# lna-plug.net
KiCad netlist of a schematic drawn in EAGLE
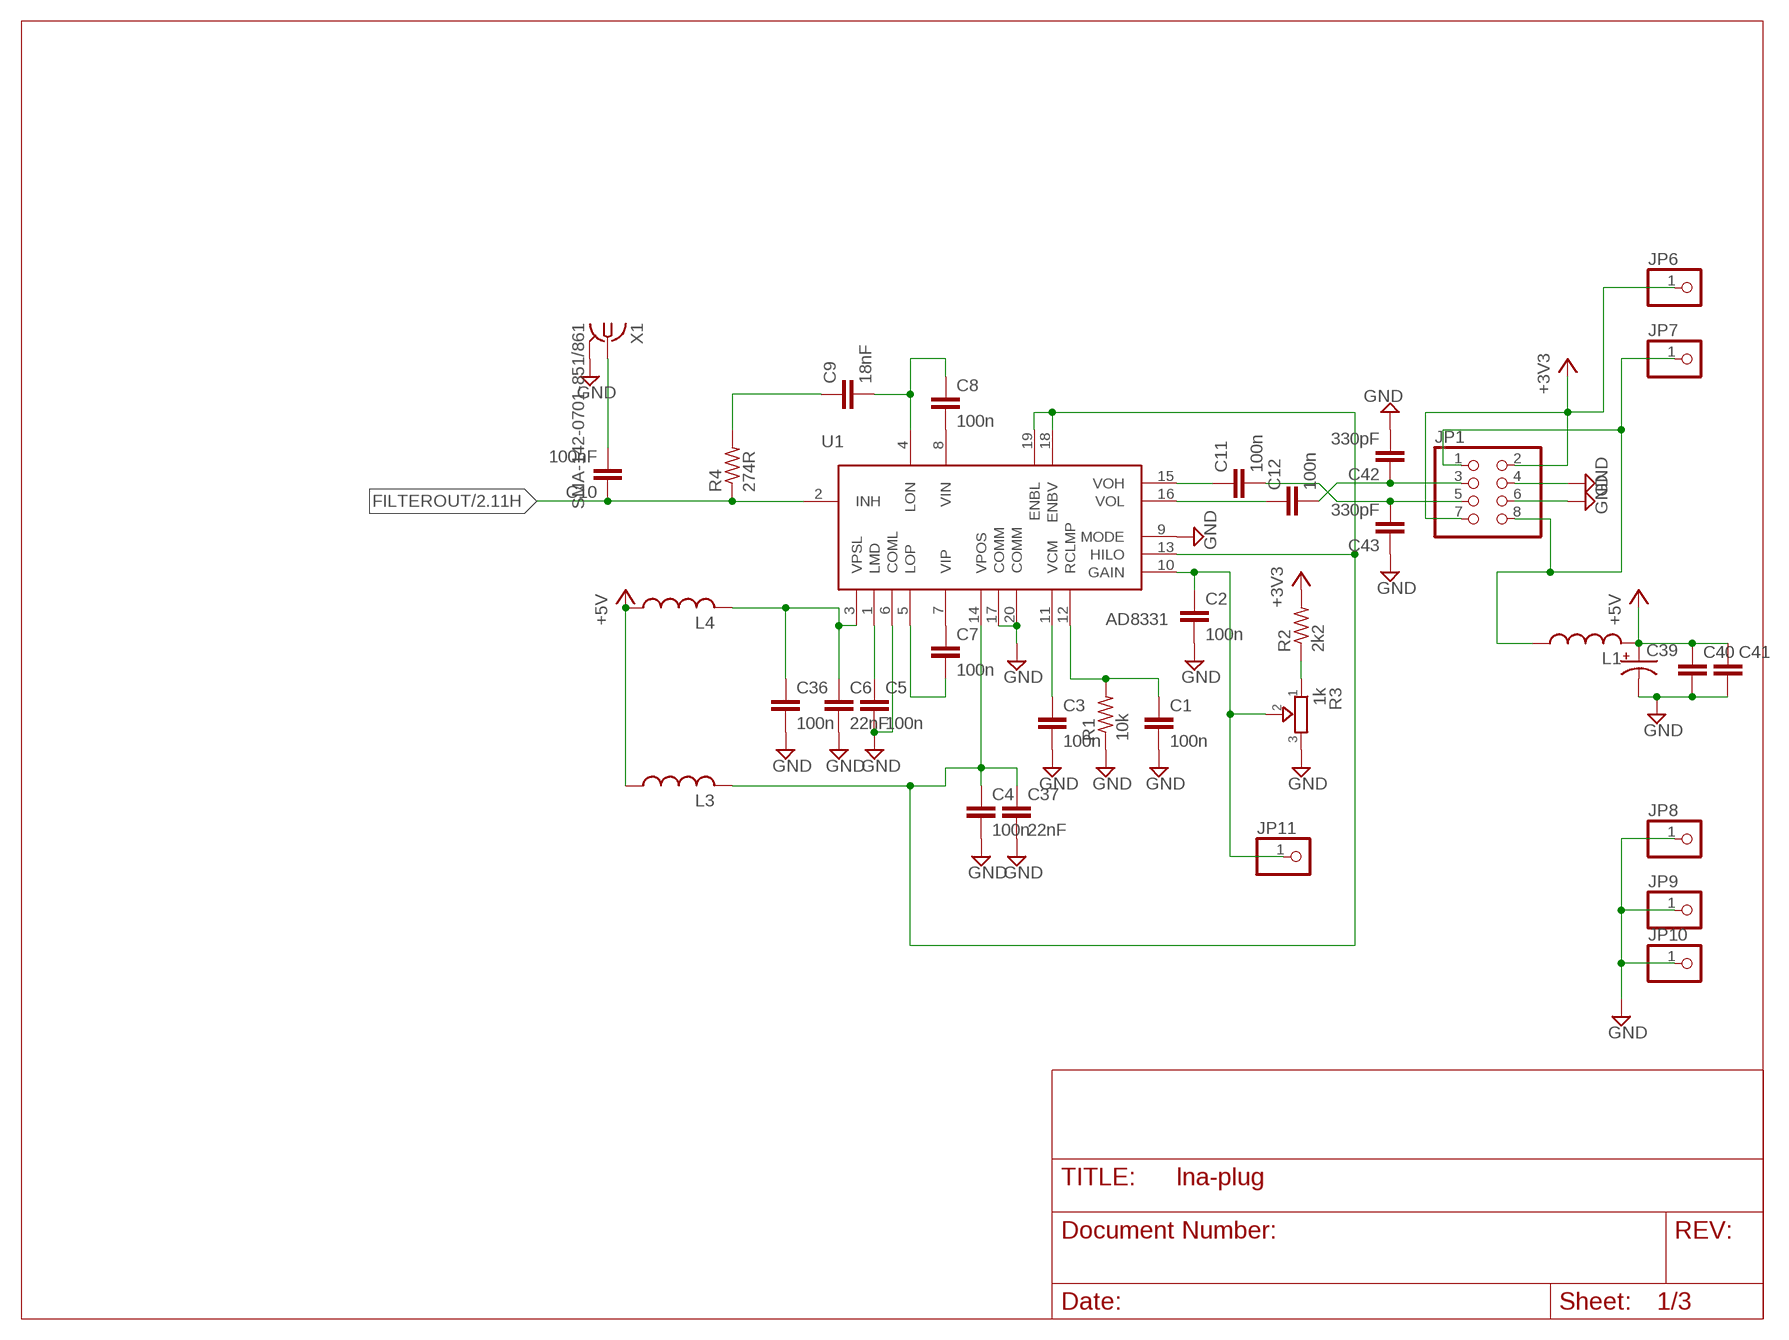
[diagram p0: schematic, sheet 1]
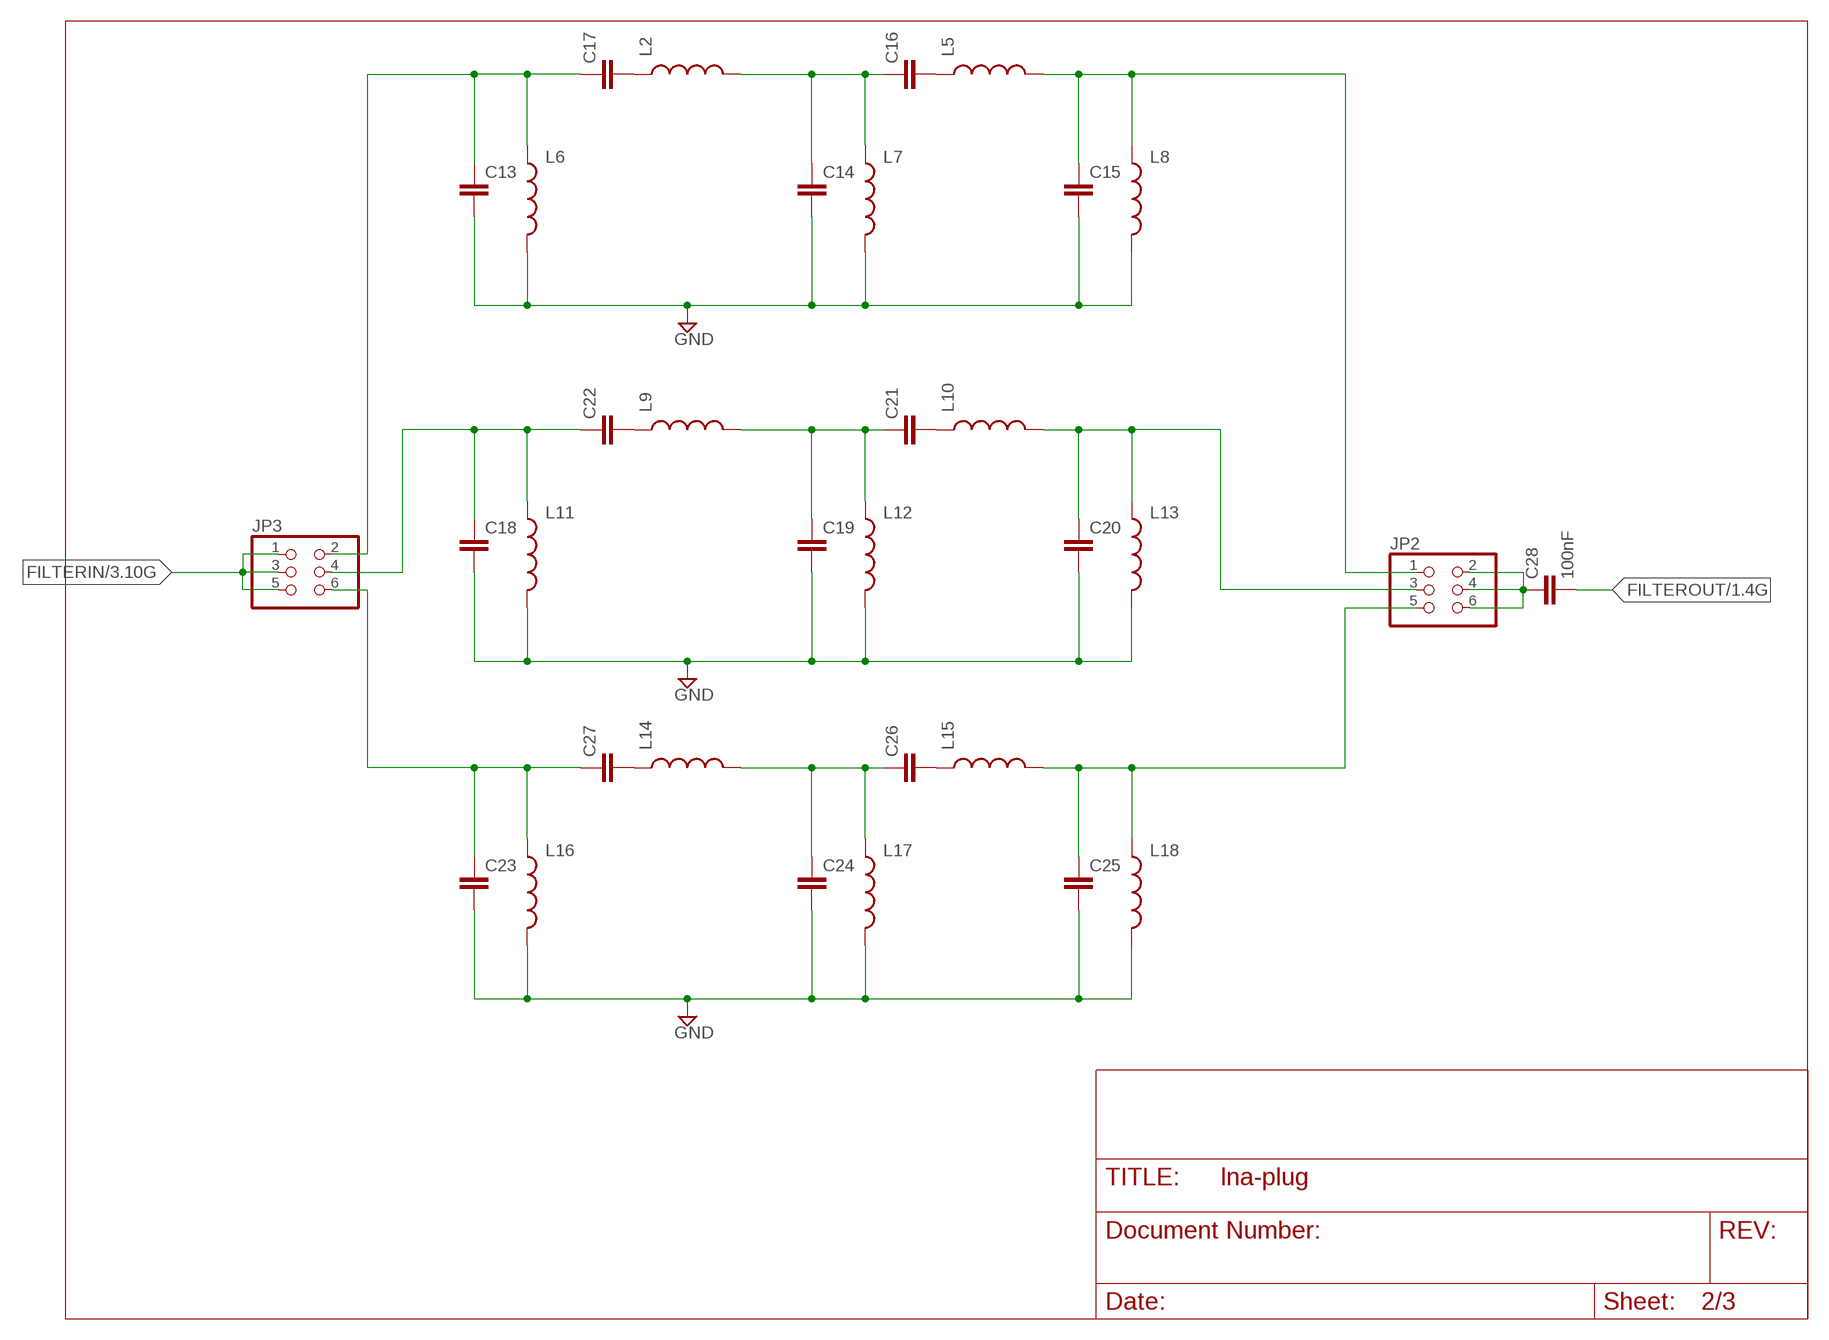
[diagram p1: schematic, sheet 2]
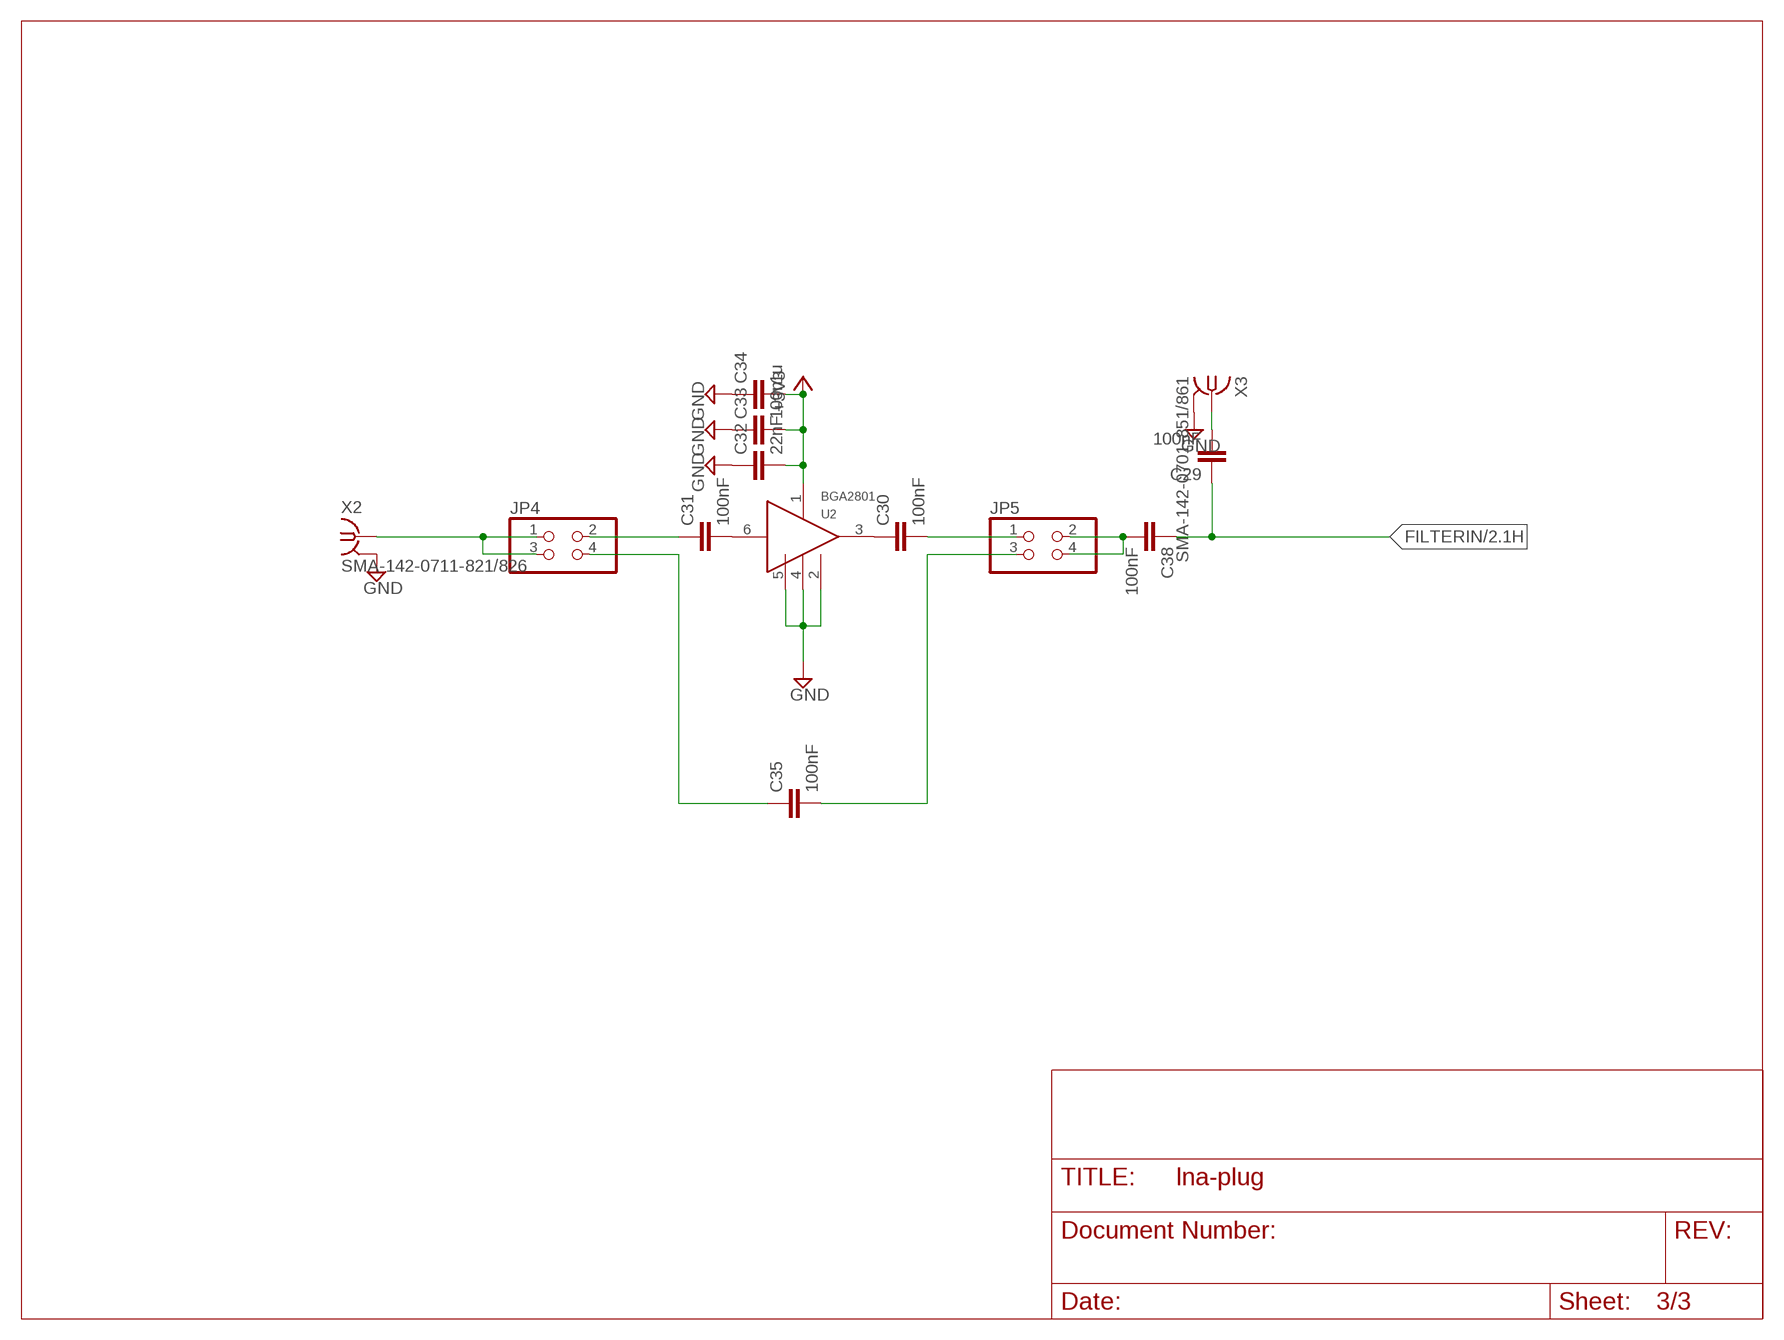
[diagram p2: schematic, sheet 3]

(export (version "E")
  (design (tool "Eeschema 10.0.6"))
  (components
    (comp (ref "C29")
      (value "100nF")
      (footprint "eagle-import:C0603")
      (libsource (lib "eagle-import") (part "resistor_C-EUC0603"))
    )
    (comp (ref "C30")
      (value "100nF")
      (footprint "eagle-import:C0603")
      (libsource (lib "eagle-import") (part "resistor_C-EUC0603"))
    )
    (comp (ref "C31")
      (value "100nF")
      (footprint "eagle-import:C0603")
      (libsource (lib "eagle-import") (part "resistor_C-EUC0603"))
    )
    (comp (ref "C32")
      (value "22nF")
      (footprint "eagle-import:C0603")
      (libsource (lib "eagle-import") (part "resistor_C-EUC0603"))
    )
    (comp (ref "C33")
      (value "100n")
      (footprint "eagle-import:C0603")
      (libsource (lib "eagle-import") (part "resistor_C-EUC0603"))
    )
    (comp (ref "C34")
      (value "1u")
      (footprint "eagle-import:C0603")
      (libsource (lib "eagle-import") (part "resistor_C-EUC0603"))
    )
    (comp (ref "C35")
      (value "100nF")
      (footprint "eagle-import:C0603")
      (libsource (lib "eagle-import") (part "resistor_C-EUC0603"))
    )
    (comp (ref "C38")
      (value "100nF")
      (footprint "eagle-import:C0603")
      (libsource (lib "eagle-import") (part "resistor_C-EUC0603"))
    )
    (comp (ref "JP4")
      (value "PINHD-2X2")
      (footprint "eagle-import:2X02")
      (libsource (lib "eagle-import") (part "PINHD-2X2"))
    )
    (comp (ref "JP5")
      (value "PINHD-2X2")
      (footprint "eagle-import:2X02")
      (libsource (lib "eagle-import") (part "PINHD-2X2"))
    )
    (comp (ref "U2")
      (value "BGA2801")
      (footprint "eagle-import:SOTT323-6")
      (libsource (lib "eagle-import") (part "BGA2801"))
    )
    (comp (ref "X2")
      (value "SMA-142-0711-821/826")
      (footprint "eagle-import:J502-ND-142-0711-821_826")
      (fields (field (name "MF") "JOHNSON COMPONENTS") (field (name "MPN") "142-0711-821"))
      (libsource (lib "eagle-import") (part "SMA-142-0711-821/826"))
    )
    (comp (ref "X3")
      (value "SMA-142-0701-851/861")
      (footprint "eagle-import:J502-ND-142-0701-851_861")
      (fields (field (name "MF") "JOHNSON COMPONENTS") (field (name "MPN") "142-0701-851"))
      (libsource (lib "eagle-import") (part "SMA-142-0701-851/861"))
    )
    (comp (ref "C1")
      (value "100n")
      (footprint "eagle-import:C0603")
      (libsource (lib "eagle-import") (part "resistor_C-EUC0603"))
    )
    (comp (ref "C2")
      (value "100n")
      (footprint "eagle-import:C0603")
      (libsource (lib "eagle-import") (part "resistor_C-EUC0603"))
    )
    (comp (ref "C3")
      (value "100n")
      (footprint "eagle-import:C0603")
      (libsource (lib "eagle-import") (part "resistor_C-EUC0603"))
    )
    (comp (ref "C4")
      (value "100n")
      (footprint "eagle-import:C0603")
      (libsource (lib "eagle-import") (part "resistor_C-EUC0603"))
    )
    (comp (ref "C5")
      (value "100n")
      (footprint "eagle-import:C0603")
      (libsource (lib "eagle-import") (part "resistor_C-EUC0603"))
    )
    (comp (ref "C6")
      (value "22nF")
      (footprint "eagle-import:C0603")
      (libsource (lib "eagle-import") (part "resistor_C-EUC0603"))
    )
    (comp (ref "C7")
      (value "100n")
      (footprint "eagle-import:C0603")
      (libsource (lib "eagle-import") (part "resistor_C-EUC0603"))
    )
    (comp (ref "C8")
      (value "100n")
      (footprint "eagle-import:C0603")
      (libsource (lib "eagle-import") (part "resistor_C-EUC0603"))
    )
    (comp (ref "C9")
      (value "18nF")
      (footprint "eagle-import:C0603")
      (libsource (lib "eagle-import") (part "resistor_C-EUC0603"))
    )
    (comp (ref "C10")
      (value "100nF")
      (footprint "eagle-import:C0603")
      (libsource (lib "eagle-import") (part "resistor_C-EUC0603"))
    )
    (comp (ref "C11")
      (value "100n")
      (footprint "eagle-import:C0603")
      (libsource (lib "eagle-import") (part "resistor_C-EUC0603"))
    )
    (comp (ref "C12")
      (value "100n")
      (footprint "eagle-import:C0603")
      (libsource (lib "eagle-import") (part "resistor_C-EUC0603"))
    )
    (comp (ref "C36")
      (value "100n")
      (footprint "eagle-import:C0603")
      (libsource (lib "eagle-import") (part "resistor_C-EUC0603"))
    )
    (comp (ref "C37")
      (value "22nF")
      (footprint "eagle-import:C0603")
      (libsource (lib "eagle-import") (part "resistor_C-EUC0603"))
    )
    (comp (ref "C39")
      (value "CPOL-USSMCC")
      (footprint "eagle-import:SMC_C")
      (libsource (lib "eagle-import") (part "CPOL-USSMCC"))
    )
    (comp (ref "C40")
      (value "C-EUC1206")
      (footprint "eagle-import:C1206")
      (libsource (lib "eagle-import") (part "C-EUC1206"))
    )
    (comp (ref "C41")
      (value "C-EUC0805")
      (footprint "eagle-import:C0805")
      (libsource (lib "eagle-import") (part "C-EUC0805"))
    )
    (comp (ref "C42")
      (value "330pF")
      (footprint "eagle-import:C0603")
      (libsource (lib "eagle-import") (part "resistor_C-EUC0603"))
    )
    (comp (ref "C43")
      (value "330pF")
      (footprint "eagle-import:C0603")
      (libsource (lib "eagle-import") (part "resistor_C-EUC0603"))
    )
    (comp (ref "JP1")
      (value "PINHD-2X4")
      (footprint "eagle-import:2X04")
      (libsource (lib "eagle-import") (part "PINHD-2X4"))
    )
    (comp (ref "JP6")
      (value "PINHD-1X1")
      (footprint "eagle-import:1X01")
      (libsource (lib "eagle-import") (part "PINHD-1X1"))
    )
    (comp (ref "JP7")
      (value "PINHD-1X1")
      (footprint "eagle-import:1X01")
      (libsource (lib "eagle-import") (part "PINHD-1X1"))
    )
    (comp (ref "JP8")
      (value "PINHD-1X1")
      (footprint "eagle-import:1X01")
      (libsource (lib "eagle-import") (part "PINHD-1X1"))
    )
    (comp (ref "JP9")
      (value "PINHD-1X1")
      (footprint "eagle-import:1X01")
      (libsource (lib "eagle-import") (part "PINHD-1X1"))
    )
    (comp (ref "JP10")
      (value "PINHD-1X1")
      (footprint "eagle-import:1X01")
      (libsource (lib "eagle-import") (part "PINHD-1X1"))
    )
    (comp (ref "JP11")
      (value "PINHD-1X1")
      (footprint "eagle-import:1X01")
      (libsource (lib "eagle-import") (part "PINHD-1X1"))
    )
    (comp (ref "L1")
      (value "L-USL2012C")
      (footprint "eagle-import:L2012C")
      (libsource (lib "eagle-import") (part "L-USL2012C"))
    )
    (comp (ref "L3")
      (value "L-USL2012C")
      (footprint "eagle-import:L2012C")
      (libsource (lib "eagle-import") (part "L-USL2012C"))
    )
    (comp (ref "L4")
      (value "L-USL2012C")
      (footprint "eagle-import:L2012C")
      (libsource (lib "eagle-import") (part "L-USL2012C"))
    )
    (comp (ref "R1")
      (value "10k")
      (footprint "eagle-import:R0603")
      (libsource (lib "eagle-import") (part "R-US_R0603"))
    )
    (comp (ref "R2")
      (value "2k2")
      (footprint "eagle-import:R0603")
      (libsource (lib "eagle-import") (part "R-US_R0603"))
    )
    (comp (ref "R3")
      (value "1k")
      (footprint "eagle-import:TRIMMER_3362P")
      (libsource (lib "eagle-import") (part "TRIMMER-3362P"))
    )
    (comp (ref "R4")
      (value "274R")
      (footprint "eagle-import:R0603")
      (libsource (lib "eagle-import") (part "R-US_R0603"))
    )
    (comp (ref "U1")
      (value "AD8331")
      (footprint "eagle-import:QSOP20")
      (libsource (lib "eagle-import") (part "AD8331"))
    )
    (comp (ref "X1")
      (value "SMA-142-0701-851/861")
      (footprint "eagle-import:J502-ND-142-0701-851_861")
      (fields (field (name "MF") "JOHNSON COMPONENTS") (field (name "MPN") "142-0701-851"))
      (libsource (lib "eagle-import") (part "SMA-142-0701-851/861"))
    )
    (comp (ref "C13")
      (value "C-EUC0603")
      (footprint "eagle-import:C0603")
      (libsource (lib "eagle-import") (part "resistor_C-EUC0603"))
    )
    (comp (ref "C14")
      (value "C-EUC0603")
      (footprint "eagle-import:C0603")
      (libsource (lib "eagle-import") (part "resistor_C-EUC0603"))
    )
    (comp (ref "C15")
      (value "C-EUC0603")
      (footprint "eagle-import:C0603")
      (libsource (lib "eagle-import") (part "resistor_C-EUC0603"))
    )
    (comp (ref "C16")
      (value "C-EUC0603")
      (footprint "eagle-import:C0603")
      (libsource (lib "eagle-import") (part "resistor_C-EUC0603"))
    )
    (comp (ref "C17")
      (value "C-EUC0603")
      (footprint "eagle-import:C0603")
      (libsource (lib "eagle-import") (part "resistor_C-EUC0603"))
    )
    (comp (ref "C18")
      (value "C-EUC0603")
      (footprint "eagle-import:C0603")
      (libsource (lib "eagle-import") (part "resistor_C-EUC0603"))
    )
    (comp (ref "C19")
      (value "C-EUC0603")
      (footprint "eagle-import:C0603")
      (libsource (lib "eagle-import") (part "resistor_C-EUC0603"))
    )
    (comp (ref "C20")
      (value "C-EUC0603")
      (footprint "eagle-import:C0603")
      (libsource (lib "eagle-import") (part "resistor_C-EUC0603"))
    )
    (comp (ref "C21")
      (value "C-EUC0603")
      (footprint "eagle-import:C0603")
      (libsource (lib "eagle-import") (part "resistor_C-EUC0603"))
    )
    (comp (ref "C22")
      (value "C-EUC0603")
      (footprint "eagle-import:C0603")
      (libsource (lib "eagle-import") (part "resistor_C-EUC0603"))
    )
    (comp (ref "C23")
      (value "C-EUC0603")
      (footprint "eagle-import:C0603")
      (libsource (lib "eagle-import") (part "resistor_C-EUC0603"))
    )
    (comp (ref "C24")
      (value "C-EUC0603")
      (footprint "eagle-import:C0603")
      (libsource (lib "eagle-import") (part "resistor_C-EUC0603"))
    )
    (comp (ref "C25")
      (value "C-EUC0603")
      (footprint "eagle-import:C0603")
      (libsource (lib "eagle-import") (part "resistor_C-EUC0603"))
    )
    (comp (ref "C26")
      (value "C-EUC0603")
      (footprint "eagle-import:C0603")
      (libsource (lib "eagle-import") (part "resistor_C-EUC0603"))
    )
    (comp (ref "C27")
      (value "C-EUC0603")
      (footprint "eagle-import:C0603")
      (libsource (lib "eagle-import") (part "resistor_C-EUC0603"))
    )
    (comp (ref "C28")
      (value "100nF")
      (footprint "eagle-import:C0603")
      (libsource (lib "eagle-import") (part "resistor_C-EUC0603"))
    )
    (comp (ref "JP2")
      (value "PINHD-2X3")
      (footprint "eagle-import:2X03")
      (libsource (lib "eagle-import") (part "PINHD-2X3"))
    )
    (comp (ref "JP3")
      (value "PINHD-2X3")
      (footprint "eagle-import:2X03")
      (libsource (lib "eagle-import") (part "PINHD-2X3"))
    )
    (comp (ref "L2")
      (value "INDUCTOR0603")
      (footprint "eagle-import:0603")
      (libsource (lib "eagle-import") (part "INDUCTOR0603"))
    )
    (comp (ref "L5")
      (value "INDUCTOR0603")
      (footprint "eagle-import:0603")
      (libsource (lib "eagle-import") (part "INDUCTOR0603"))
    )
    (comp (ref "L6")
      (value "INDUCTOR0603")
      (footprint "eagle-import:0603")
      (libsource (lib "eagle-import") (part "INDUCTOR0603"))
    )
    (comp (ref "L7")
      (value "INDUCTOR0603")
      (footprint "eagle-import:0603")
      (libsource (lib "eagle-import") (part "INDUCTOR0603"))
    )
    (comp (ref "L8")
      (value "INDUCTOR0603")
      (footprint "eagle-import:0603")
      (libsource (lib "eagle-import") (part "INDUCTOR0603"))
    )
    (comp (ref "L9")
      (value "INDUCTOR0603")
      (footprint "eagle-import:0603")
      (libsource (lib "eagle-import") (part "INDUCTOR0603"))
    )
    (comp (ref "L10")
      (value "INDUCTOR0603")
      (footprint "eagle-import:0603")
      (libsource (lib "eagle-import") (part "INDUCTOR0603"))
    )
    (comp (ref "L11")
      (value "INDUCTOR0603")
      (footprint "eagle-import:0603")
      (libsource (lib "eagle-import") (part "INDUCTOR0603"))
    )
    (comp (ref "L12")
      (value "INDUCTOR0603")
      (footprint "eagle-import:0603")
      (libsource (lib "eagle-import") (part "INDUCTOR0603"))
    )
    (comp (ref "L13")
      (value "INDUCTOR0603")
      (footprint "eagle-import:0603")
      (libsource (lib "eagle-import") (part "INDUCTOR0603"))
    )
    (comp (ref "L14")
      (value "INDUCTOR0603")
      (footprint "eagle-import:0603")
      (libsource (lib "eagle-import") (part "INDUCTOR0603"))
    )
    (comp (ref "L15")
      (value "INDUCTOR0603")
      (footprint "eagle-import:0603")
      (libsource (lib "eagle-import") (part "INDUCTOR0603"))
    )
    (comp (ref "L16")
      (value "INDUCTOR0603")
      (footprint "eagle-import:0603")
      (libsource (lib "eagle-import") (part "INDUCTOR0603"))
    )
    (comp (ref "L17")
      (value "INDUCTOR0603")
      (footprint "eagle-import:0603")
      (libsource (lib "eagle-import") (part "INDUCTOR0603"))
    )
    (comp (ref "L18")
      (value "INDUCTOR0603")
      (footprint "eagle-import:0603")
      (libsource (lib "eagle-import") (part "INDUCTOR0603"))
    )
  )
  (nets
    (net (code "1") (name "+3V3") (class "Default")
      (node (ref "C32") (pin "2") (pinfunction "2_2") (pintype "passive"))
      (node (ref "C33") (pin "2") (pinfunction "2_2") (pintype "passive"))
      (node (ref "C34") (pin "2") (pinfunction "2_2") (pintype "passive"))
      (node (ref "JP1") (pin "2") (pinfunction "2_2") (pintype "passive"))
      (node (ref "JP1") (pin "7") (pinfunction "7_7") (pintype "passive"))
      (node (ref "JP6") (pin "1") (pinfunction "1_1") (pintype "passive"))
      (node (ref "R2") (pin "2") (pinfunction "2_2") (pintype "passive"))
      (node (ref "U2") (pin "1") (pinfunction "VCC_1") (pintype "bidirectional"))
    )
    (net (code "2") (name "+5V") (class "Default")
      (node (ref "C39") (pin "+") (pinfunction "+_+") (pintype "passive"))
      (node (ref "C40") (pin "1") (pinfunction "1_1") (pintype "passive"))
      (node (ref "C41") (pin "1") (pinfunction "1_1") (pintype "passive"))
      (node (ref "L1") (pin "2") (pinfunction "2_2") (pintype "passive"))
      (node (ref "L3") (pin "1") (pinfunction "1_1") (pintype "passive"))
      (node (ref "L4") (pin "1") (pinfunction "1_1") (pintype "passive"))
    )
    (net (code "3") (name "FILTERIN") (class "Default")
      (node (ref "C29") (pin "1") (pinfunction "1_1") (pintype "passive"))
      (node (ref "C38") (pin "1") (pinfunction "1_1") (pintype "passive"))
      (node (ref "JP3") (pin "1") (pinfunction "1_1") (pintype "passive"))
      (node (ref "JP3") (pin "3") (pinfunction "3_3") (pintype "passive"))
      (node (ref "JP3") (pin "5") (pinfunction "5_5") (pintype "passive"))
    )
    (net (code "4") (name "FILTEROUT") (class "Default")
      (node (ref "C10") (pin "1") (pinfunction "1_1") (pintype "passive"))
      (node (ref "C28") (pin "2") (pinfunction "2_2") (pintype "passive"))
      (node (ref "R4") (pin "1") (pinfunction "1_1") (pintype "passive"))
      (node (ref "U1") (pin "2") (pinfunction "INH_2") (pintype "bidirectional"))
    )
    (net (code "5") (name "GND") (class "Default")
      (node (ref "C1") (pin "2") (pinfunction "2_2") (pintype "passive"))
      (node (ref "C13") (pin "2") (pinfunction "2_2") (pintype "passive"))
      (node (ref "C14") (pin "2") (pinfunction "2_2") (pintype "passive"))
      (node (ref "C15") (pin "2") (pinfunction "2_2") (pintype "passive"))
      (node (ref "C18") (pin "2") (pinfunction "2_2") (pintype "passive"))
      (node (ref "C19") (pin "2") (pinfunction "2_2") (pintype "passive"))
      (node (ref "C2") (pin "2") (pinfunction "2_2") (pintype "passive"))
      (node (ref "C20") (pin "2") (pinfunction "2_2") (pintype "passive"))
      (node (ref "C23") (pin "2") (pinfunction "2_2") (pintype "passive"))
      (node (ref "C24") (pin "2") (pinfunction "2_2") (pintype "passive"))
      (node (ref "C25") (pin "2") (pinfunction "2_2") (pintype "passive"))
      (node (ref "C3") (pin "2") (pinfunction "2_2") (pintype "passive"))
      (node (ref "C32") (pin "1") (pinfunction "1_1") (pintype "passive"))
      (node (ref "C33") (pin "1") (pinfunction "1_1") (pintype "passive"))
      (node (ref "C34") (pin "1") (pinfunction "1_1") (pintype "passive"))
      (node (ref "C36") (pin "2") (pinfunction "2_2") (pintype "passive"))
      (node (ref "C37") (pin "2") (pinfunction "2_2") (pintype "passive"))
      (node (ref "C39") (pin "-") (pinfunction "-_-") (pintype "passive"))
      (node (ref "C4") (pin "2") (pinfunction "2_2") (pintype "passive"))
      (node (ref "C40") (pin "2") (pinfunction "2_2") (pintype "passive"))
      (node (ref "C41") (pin "2") (pinfunction "2_2") (pintype "passive"))
      (node (ref "C42") (pin "2") (pinfunction "2_2") (pintype "passive"))
      (node (ref "C43") (pin "1") (pinfunction "1_1") (pintype "passive"))
      (node (ref "C5") (pin "2") (pinfunction "2_2") (pintype "passive"))
      (node (ref "C6") (pin "2") (pinfunction "2_2") (pintype "passive"))
      (node (ref "JP1") (pin "4") (pinfunction "4_4") (pintype "passive"))
      (node (ref "JP1") (pin "6") (pinfunction "6_6") (pintype "passive"))
      (node (ref "JP10") (pin "1") (pinfunction "1_1") (pintype "passive"))
      (node (ref "JP8") (pin "1") (pinfunction "1_1") (pintype "passive"))
      (node (ref "JP9") (pin "1") (pinfunction "1_1") (pintype "passive"))
      (node (ref "L11") (pin "2") (pinfunction "2_2") (pintype "passive"))
      (node (ref "L12") (pin "2") (pinfunction "2_2") (pintype "passive"))
      (node (ref "L13") (pin "2") (pinfunction "2_2") (pintype "passive"))
      (node (ref "L16") (pin "2") (pinfunction "2_2") (pintype "passive"))
      (node (ref "L17") (pin "2") (pinfunction "2_2") (pintype "passive"))
      (node (ref "L18") (pin "2") (pinfunction "2_2") (pintype "passive"))
      (node (ref "L6") (pin "2") (pinfunction "2_2") (pintype "passive"))
      (node (ref "L7") (pin "2") (pinfunction "2_2") (pintype "passive"))
      (node (ref "L8") (pin "2") (pinfunction "2_2") (pintype "passive"))
      (node (ref "R1") (pin "1") (pinfunction "1_1") (pintype "passive"))
      (node (ref "R3") (pin "3") (pinfunction "3_3") (pintype "passive"))
      (node (ref "U1") (pin "17") (pinfunction "COMM_17") (pintype "bidirectional"))
      (node (ref "U1") (pin "20") (pinfunction "COMM_20") (pintype "bidirectional"))
      (node (ref "U1") (pin "6") (pinfunction "COML_6") (pintype "bidirectional"))
      (node (ref "U1") (pin "9") (pinfunction "MODE_9") (pintype "bidirectional"))
      (node (ref "U2") (pin "2") (pinfunction "GND_2") (pintype "bidirectional"))
      (node (ref "U2") (pin "4") (pinfunction "GND_4") (pintype "bidirectional"))
      (node (ref "U2") (pin "5") (pinfunction "GND_5") (pintype "bidirectional"))
      (node (ref "X1") (pin "G@1") (pinfunction "2_G@1") (pintype "passive"))
      (node (ref "X1") (pin "G@2") (pinfunction "2_G@2") (pintype "passive"))
      (node (ref "X1") (pin "G@3") (pinfunction "2_G@3") (pintype "passive"))
      (node (ref "X1") (pin "G@4") (pinfunction "2_G@4") (pintype "passive"))
      (node (ref "X2") (pin "G@1") (pinfunction "2_G@1") (pintype "passive"))
      (node (ref "X2") (pin "G@2") (pinfunction "2_G@2") (pintype "passive"))
      (node (ref "X2") (pin "G@3") (pinfunction "2_G@3") (pintype "passive"))
      (node (ref "X2") (pin "G@4") (pinfunction "2_G@4") (pintype "passive"))
      (node (ref "X3") (pin "G@1") (pinfunction "2_G@1") (pintype "passive"))
      (node (ref "X3") (pin "G@2") (pinfunction "2_G@2") (pintype "passive"))
      (node (ref "X3") (pin "G@3") (pinfunction "2_G@3") (pintype "passive"))
      (node (ref "X3") (pin "G@4") (pinfunction "2_G@4") (pintype "passive"))
    )
    (net (code "6") (name "Net-(C9-Pad1)") (class "Default")
      (node (ref "C9") (pin "1") (pinfunction "1_1") (pintype "passive"))
      (node (ref "R4") (pin "2") (pinfunction "2_2") (pintype "passive"))
    )
    (net (code "7") (name "Net-(C10-Pad2)") (class "Default")
      (node (ref "C10") (pin "2") (pinfunction "2_2") (pintype "passive"))
      (node (ref "X1") (pin "1") (pinfunction "1_1") (pintype "passive"))
    )
    (net (code "8") (name "Net-(C11-Pad2)") (class "Default")
      (node (ref "C11") (pin "2") (pinfunction "2_2") (pintype "passive"))
      (node (ref "C43") (pin "2") (pinfunction "2_2") (pintype "passive"))
      (node (ref "JP1") (pin "5") (pinfunction "5_5") (pintype "passive"))
    )
    (net (code "9") (name "Net-(C12-Pad2)") (class "Default")
      (node (ref "C12") (pin "2") (pinfunction "2_2") (pintype "passive"))
      (node (ref "C42") (pin "1") (pinfunction "1_1") (pintype "passive"))
      (node (ref "JP1") (pin "3") (pinfunction "3_3") (pintype "passive"))
    )
    (net (code "10") (name "Net-(C13-Pad1)") (class "Default")
      (node (ref "C13") (pin "1") (pinfunction "1_1") (pintype "passive"))
      (node (ref "C17") (pin "1") (pinfunction "1_1") (pintype "passive"))
      (node (ref "JP3") (pin "2") (pinfunction "2_2") (pintype "passive"))
      (node (ref "L6") (pin "1") (pinfunction "1_1") (pintype "passive"))
    )
    (net (code "11") (name "Net-(C14-Pad1)") (class "Default")
      (node (ref "C14") (pin "1") (pinfunction "1_1") (pintype "passive"))
      (node (ref "C16") (pin "1") (pinfunction "1_1") (pintype "passive"))
      (node (ref "L2") (pin "2") (pinfunction "2_2") (pintype "passive"))
      (node (ref "L7") (pin "1") (pinfunction "1_1") (pintype "passive"))
    )
    (net (code "12") (name "Net-(C15-Pad1)") (class "Default")
      (node (ref "C15") (pin "1") (pinfunction "1_1") (pintype "passive"))
      (node (ref "JP2") (pin "1") (pinfunction "1_1") (pintype "passive"))
      (node (ref "L5") (pin "2") (pinfunction "2_2") (pintype "passive"))
      (node (ref "L8") (pin "1") (pinfunction "1_1") (pintype "passive"))
    )
    (net (code "13") (name "Net-(C16-Pad2)") (class "Default")
      (node (ref "C16") (pin "2") (pinfunction "2_2") (pintype "passive"))
      (node (ref "L5") (pin "1") (pinfunction "1_1") (pintype "passive"))
    )
    (net (code "14") (name "Net-(C17-Pad2)") (class "Default")
      (node (ref "C17") (pin "2") (pinfunction "2_2") (pintype "passive"))
      (node (ref "L2") (pin "1") (pinfunction "1_1") (pintype "passive"))
    )
    (net (code "15") (name "Net-(C18-Pad1)") (class "Default")
      (node (ref "C18") (pin "1") (pinfunction "1_1") (pintype "passive"))
      (node (ref "C22") (pin "1") (pinfunction "1_1") (pintype "passive"))
      (node (ref "JP3") (pin "4") (pinfunction "4_4") (pintype "passive"))
      (node (ref "L11") (pin "1") (pinfunction "1_1") (pintype "passive"))
    )
    (net (code "16") (name "Net-(C19-Pad1)") (class "Default")
      (node (ref "C19") (pin "1") (pinfunction "1_1") (pintype "passive"))
      (node (ref "C21") (pin "1") (pinfunction "1_1") (pintype "passive"))
      (node (ref "L12") (pin "1") (pinfunction "1_1") (pintype "passive"))
      (node (ref "L9") (pin "2") (pinfunction "2_2") (pintype "passive"))
    )
    (net (code "17") (name "Net-(C20-Pad1)") (class "Default")
      (node (ref "C20") (pin "1") (pinfunction "1_1") (pintype "passive"))
      (node (ref "JP2") (pin "3") (pinfunction "3_3") (pintype "passive"))
      (node (ref "L10") (pin "2") (pinfunction "2_2") (pintype "passive"))
      (node (ref "L13") (pin "1") (pinfunction "1_1") (pintype "passive"))
    )
    (net (code "18") (name "Net-(C21-Pad2)") (class "Default")
      (node (ref "C21") (pin "2") (pinfunction "2_2") (pintype "passive"))
      (node (ref "L10") (pin "1") (pinfunction "1_1") (pintype "passive"))
    )
    (net (code "19") (name "Net-(C22-Pad2)") (class "Default")
      (node (ref "C22") (pin "2") (pinfunction "2_2") (pintype "passive"))
      (node (ref "L9") (pin "1") (pinfunction "1_1") (pintype "passive"))
    )
    (net (code "20") (name "Net-(C23-Pad1)") (class "Default")
      (node (ref "C23") (pin "1") (pinfunction "1_1") (pintype "passive"))
      (node (ref "C27") (pin "1") (pinfunction "1_1") (pintype "passive"))
      (node (ref "JP3") (pin "6") (pinfunction "6_6") (pintype "passive"))
      (node (ref "L16") (pin "1") (pinfunction "1_1") (pintype "passive"))
    )
    (net (code "21") (name "Net-(C24-Pad1)") (class "Default")
      (node (ref "C24") (pin "1") (pinfunction "1_1") (pintype "passive"))
      (node (ref "C26") (pin "1") (pinfunction "1_1") (pintype "passive"))
      (node (ref "L14") (pin "2") (pinfunction "2_2") (pintype "passive"))
      (node (ref "L17") (pin "1") (pinfunction "1_1") (pintype "passive"))
    )
    (net (code "22") (name "Net-(C25-Pad1)") (class "Default")
      (node (ref "C25") (pin "1") (pinfunction "1_1") (pintype "passive"))
      (node (ref "JP2") (pin "5") (pinfunction "5_5") (pintype "passive"))
      (node (ref "L15") (pin "2") (pinfunction "2_2") (pintype "passive"))
      (node (ref "L18") (pin "1") (pinfunction "1_1") (pintype "passive"))
    )
    (net (code "23") (name "Net-(C26-Pad2)") (class "Default")
      (node (ref "C26") (pin "2") (pinfunction "2_2") (pintype "passive"))
      (node (ref "L15") (pin "1") (pinfunction "1_1") (pintype "passive"))
    )
    (net (code "24") (name "Net-(C27-Pad2)") (class "Default")
      (node (ref "C27") (pin "2") (pinfunction "2_2") (pintype "passive"))
      (node (ref "L14") (pin "1") (pinfunction "1_1") (pintype "passive"))
    )
    (net (code "25") (name "Net-(C28-Pad1)") (class "Default")
      (node (ref "C28") (pin "1") (pinfunction "1_1") (pintype "passive"))
      (node (ref "JP2") (pin "2") (pinfunction "2_2") (pintype "passive"))
      (node (ref "JP2") (pin "4") (pinfunction "4_4") (pintype "passive"))
      (node (ref "JP2") (pin "6") (pinfunction "6_6") (pintype "passive"))
    )
    (net (code "26") (name "Net-(C29-Pad2)") (class "Default")
      (node (ref "C29") (pin "2") (pinfunction "2_2") (pintype "passive"))
      (node (ref "X3") (pin "1") (pinfunction "1_1") (pintype "passive"))
    )
    (net (code "27") (name "Net-(C30-Pad2)") (class "Default")
      (node (ref "C30") (pin "2") (pinfunction "2_2") (pintype "passive"))
      (node (ref "JP5") (pin "1") (pinfunction "1_1") (pintype "passive"))
    )
    (net (code "28") (name "Net-(C31-Pad1)") (class "Default")
      (node (ref "C31") (pin "1") (pinfunction "1_1") (pintype "passive"))
      (node (ref "JP4") (pin "2") (pinfunction "2_2") (pintype "passive"))
    )
    (net (code "29") (name "Net-(C35-Pad1)") (class "Default")
      (node (ref "C35") (pin "1") (pinfunction "1_1") (pintype "passive"))
      (node (ref "JP4") (pin "4") (pinfunction "4_4") (pintype "passive"))
    )
    (net (code "30") (name "Net-(C35-Pad2)") (class "Default")
      (node (ref "C35") (pin "2") (pinfunction "2_2") (pintype "passive"))
      (node (ref "JP5") (pin "3") (pinfunction "3_3") (pintype "passive"))
    )
    (net (code "31") (name "Net-(C38-Pad2)") (class "Default")
      (node (ref "C38") (pin "2") (pinfunction "2_2") (pintype "passive"))
      (node (ref "JP5") (pin "2") (pinfunction "2_2") (pintype "passive"))
      (node (ref "JP5") (pin "4") (pinfunction "4_4") (pintype "passive"))
    )
    (net (code "32") (name "Net-(JP1-Pad1)") (class "Default")
      (node (ref "JP1") (pin "1") (pinfunction "1_1") (pintype "passive"))
      (node (ref "JP1") (pin "8") (pinfunction "8_8") (pintype "passive"))
      (node (ref "JP7") (pin "1") (pinfunction "1_1") (pintype "passive"))
      (node (ref "L1") (pin "1") (pinfunction "1_1") (pintype "passive"))
    )
    (net (code "33") (name "Net-(JP4-Pad1)") (class "Default")
      (node (ref "JP4") (pin "1") (pinfunction "1_1") (pintype "passive"))
      (node (ref "JP4") (pin "3") (pinfunction "3_3") (pintype "passive"))
      (node (ref "X2") (pin "1") (pinfunction "1_1") (pintype "passive"))
    )
    (net (code "34") (name "Net-(R2-Pad1)") (class "Default")
      (node (ref "R2") (pin "1") (pinfunction "1_1") (pintype "passive"))
      (node (ref "R3") (pin "1") (pinfunction "1_1") (pintype "passive"))
    )
    (net (code "35") (name "Net-(U1-ENBL)") (class "Default")
      (node (ref "C37") (pin "1") (pinfunction "1_1") (pintype "passive"))
      (node (ref "C4") (pin "1") (pinfunction "1_1") (pintype "passive"))
      (node (ref "L3") (pin "2") (pinfunction "2_2") (pintype "passive"))
      (node (ref "U1") (pin "13") (pinfunction "HILO_13") (pintype "bidirectional"))
      (node (ref "U1") (pin "14") (pinfunction "VPOS_14") (pintype "bidirectional"))
      (node (ref "U1") (pin "18") (pinfunction "ENBV_18") (pintype "bidirectional"))
      (node (ref "U1") (pin "19") (pinfunction "ENBL_19") (pintype "bidirectional"))
    )
    (net (code "36") (name "Net-(U1-GAIN)") (class "Default")
      (node (ref "C2") (pin "1") (pinfunction "1_1") (pintype "passive"))
      (node (ref "JP11") (pin "1") (pinfunction "1_1") (pintype "passive"))
      (node (ref "R3") (pin "2") (pinfunction "2_2") (pintype "passive"))
      (node (ref "U1") (pin "10") (pinfunction "GAIN_10") (pintype "bidirectional"))
    )
    (net (code "37") (name "Net-(U1-LMD)") (class "Default")
      (node (ref "C5") (pin "1") (pinfunction "1_1") (pintype "passive"))
      (node (ref "U1") (pin "1") (pinfunction "LMD_1") (pintype "bidirectional"))
    )
    (net (code "38") (name "Net-(U1-LON)") (class "Default")
      (node (ref "C8") (pin "1") (pinfunction "1_1") (pintype "passive"))
      (node (ref "C9") (pin "2") (pinfunction "2_2") (pintype "passive"))
      (node (ref "U1") (pin "4") (pinfunction "LON_4") (pintype "bidirectional"))
    )
    (net (code "39") (name "Net-(U1-LOP)") (class "Default")
      (node (ref "C7") (pin "2") (pinfunction "2_2") (pintype "passive"))
      (node (ref "U1") (pin "5") (pinfunction "LOP_5") (pintype "bidirectional"))
    )
    (net (code "40") (name "Net-(U1-RCLMP)") (class "Default")
      (node (ref "C1") (pin "1") (pinfunction "1_1") (pintype "passive"))
      (node (ref "R1") (pin "2") (pinfunction "2_2") (pintype "passive"))
      (node (ref "U1") (pin "12") (pinfunction "RCLMP_12") (pintype "bidirectional"))
    )
    (net (code "41") (name "Net-(U1-VCM)") (class "Default")
      (node (ref "C3") (pin "1") (pinfunction "1_1") (pintype "passive"))
      (node (ref "U1") (pin "11") (pinfunction "VCM_11") (pintype "bidirectional"))
    )
    (net (code "42") (name "Net-(U1-VIN)") (class "Default")
      (node (ref "C8") (pin "2") (pinfunction "2_2") (pintype "passive"))
      (node (ref "U1") (pin "8") (pinfunction "VIN_8") (pintype "bidirectional"))
    )
    (net (code "43") (name "Net-(U1-VIP)") (class "Default")
      (node (ref "C7") (pin "1") (pinfunction "1_1") (pintype "passive"))
      (node (ref "U1") (pin "7") (pinfunction "VIP_7") (pintype "bidirectional"))
    )
    (net (code "44") (name "Net-(U1-VOH)") (class "Default")
      (node (ref "C11") (pin "1") (pinfunction "1_1") (pintype "passive"))
      (node (ref "U1") (pin "15") (pinfunction "VOH_15") (pintype "bidirectional"))
    )
    (net (code "45") (name "Net-(U1-VOL)") (class "Default")
      (node (ref "C12") (pin "1") (pinfunction "1_1") (pintype "passive"))
      (node (ref "U1") (pin "16") (pinfunction "VOL_16") (pintype "bidirectional"))
    )
    (net (code "46") (name "Net-(U1-VPSL)") (class "Default")
      (node (ref "C36") (pin "1") (pinfunction "1_1") (pintype "passive"))
      (node (ref "C6") (pin "1") (pinfunction "1_1") (pintype "passive"))
      (node (ref "L4") (pin "2") (pinfunction "2_2") (pintype "passive"))
      (node (ref "U1") (pin "3") (pinfunction "VPSL_3") (pintype "bidirectional"))
    )
    (net (code "47") (name "Net-(U2-IN)") (class "Default")
      (node (ref "C31") (pin "2") (pinfunction "2_2") (pintype "passive"))
      (node (ref "U2") (pin "6") (pinfunction "IN_6") (pintype "bidirectional"))
    )
    (net (code "48") (name "Net-(U2-OUT)") (class "Default")
      (node (ref "C30") (pin "1") (pinfunction "1_1") (pintype "passive"))
      (node (ref "U2") (pin "3") (pinfunction "OUT_3") (pintype "bidirectional"))
    )
  )
)
